# QSD675-Prototype.net
KiCad netlist of a schematic drawn in EAGLE
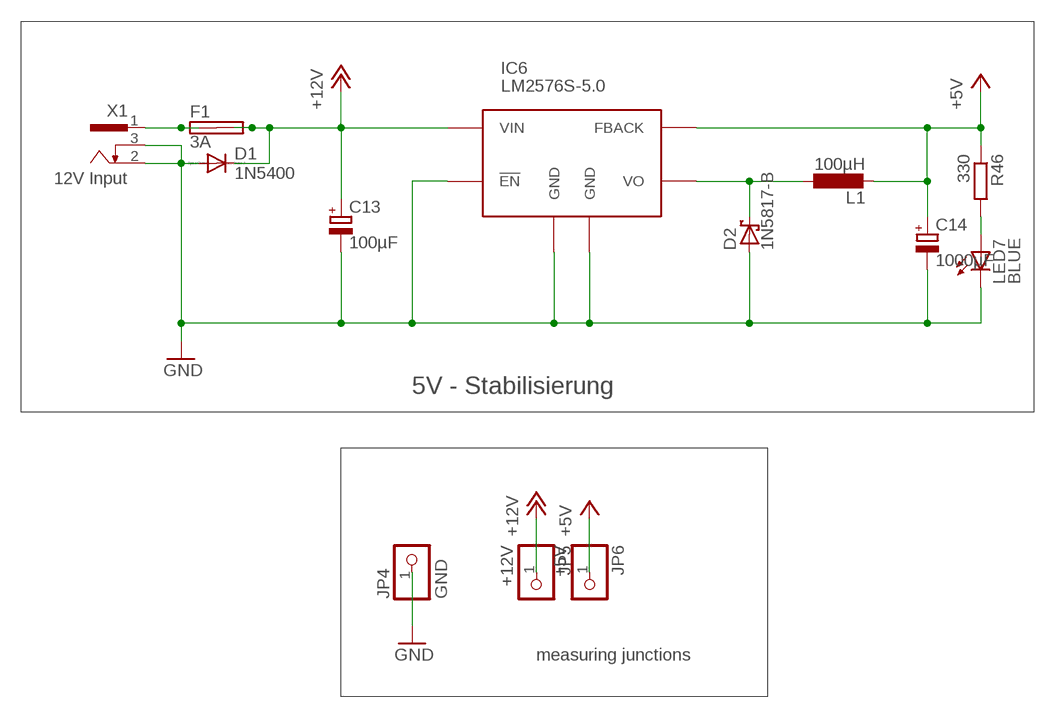
[diagram p0: schematic, sheet 1]
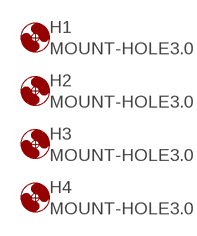
[diagram p1: schematic, sheet 2]
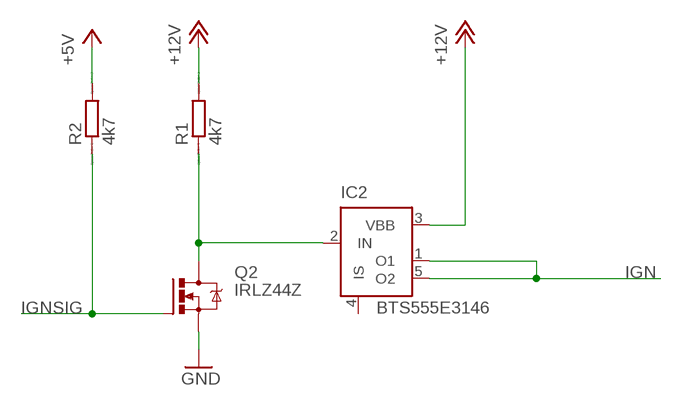
[diagram p2: schematic, sheet 3]
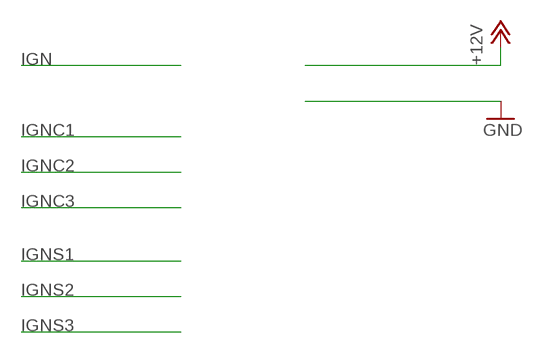
[diagram p3: schematic, sheet 5]
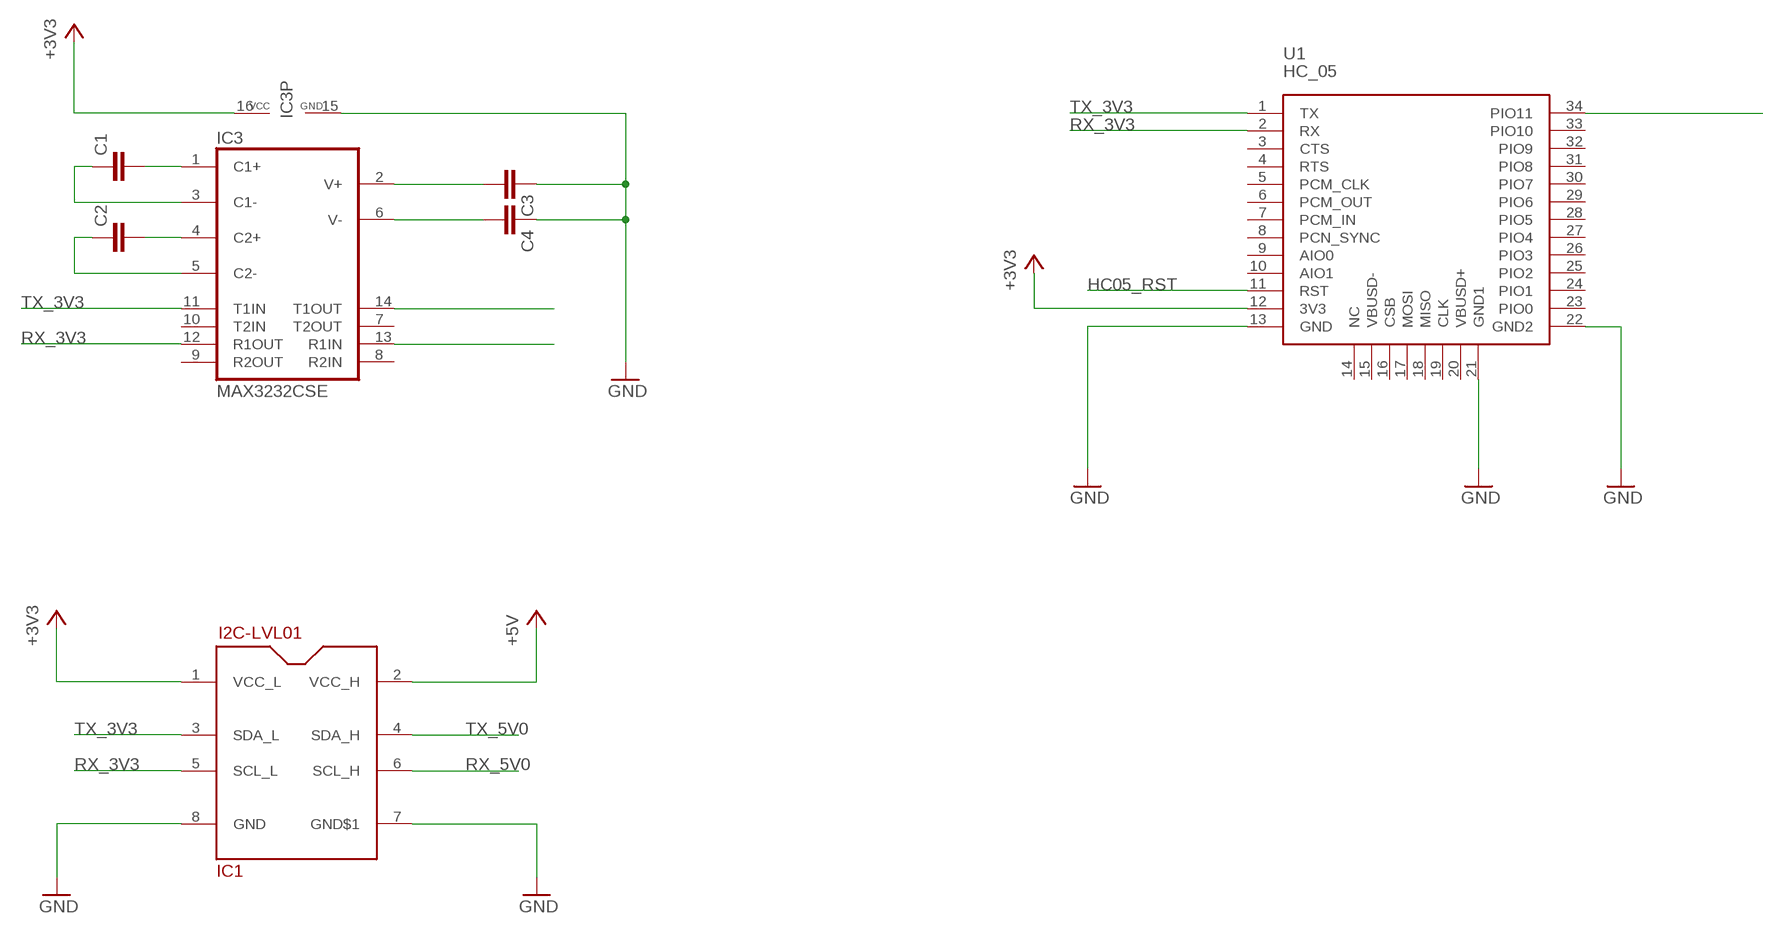
[diagram p4: schematic, sheet 6]

(export (version "E")
  (design (tool "Eeschema 10.0.6"))
  (components
    (comp (ref "C13")
      (value "100µF")
      (footprint "eagle-import:E2,5-7")
      (libsource (lib "eagle-import") (part "CPOL-EUE2.5-7"))
    )
    (comp (ref "C14")
      (value "1000µF")
      (footprint "eagle-import:E5-10,5")
      (libsource (lib "eagle-import") (part "CPOL-EUE5-10.5"))
    )
    (comp (ref "D1")
      (value "1N5400")
      (footprint "eagle-import:DO201-15")
      (libsource (lib "eagle-import") (part "1N5400"))
    )
    (comp (ref "D2")
      (value "1N5817-B")
      (footprint "eagle-import:DO41-7.6")
      (libsource (lib "eagle-import") (part "1N5817-B"))
    )
    (comp (ref "F1")
      (value "3A")
      (footprint "eagle-import:SH32")
      (fields (field (name "MPN") "10207101009"))
      (libsource (lib "eagle-import") (part "SH32"))
    )
    (comp (ref "IC6")
      (value "LM2576S-5.0")
      (footprint "eagle-import:TO263-5")
      (libsource (lib "eagle-import") (part "LM2576S"))
    )
    (comp (ref "JP4")
      (value "GND")
      (footprint "eagle-import:1X01")
      (libsource (lib "eagle-import") (part "PINHD-1X1"))
    )
    (comp (ref "JP5")
      (value "+12V")
      (footprint "eagle-import:1X01")
      (libsource (lib "eagle-import") (part "PINHD-1X1"))
    )
    (comp (ref "JP6")
      (value "+5V")
      (footprint "eagle-import:1X01")
      (libsource (lib "eagle-import") (part "PINHD-1X1"))
    )
    (comp (ref "L1")
      (value "100µH")
      (footprint "eagle-import:0204_5")
      (libsource (lib "eagle-import") (part "L-EU0204/5"))
    )
    (comp (ref "LED7")
      (value "BLUE")
      (footprint "eagle-import:SML0805")
      (libsource (lib "eagle-import") (part "LEDSML0805"))
    )
    (comp (ref "R46")
      (value "330")
      (footprint "eagle-import:M0805")
      (libsource (lib "eagle-import") (part "R-EU_M0805"))
    )
    (comp (ref "X1")
      (value "12V Input")
      (footprint "eagle-import:733980-62")
      (libsource (lib "eagle-import") (part "73398?0-62"))
    )
    (comp (ref "C1")
      (value "C-EUC0805")
      (footprint "eagle-import:C0805")
      (libsource (lib "eagle-import") (part "C-EUC0805"))
    )
    (comp (ref "C2")
      (value "C-EUC0805")
      (footprint "eagle-import:C0805")
      (libsource (lib "eagle-import") (part "C-EUC0805"))
    )
    (comp (ref "C3")
      (value "C-EUC0805")
      (footprint "eagle-import:C0805")
      (libsource (lib "eagle-import") (part "C-EUC0805"))
    )
    (comp (ref "C4")
      (value "C-EUC0805")
      (footprint "eagle-import:C0805")
      (libsource (lib "eagle-import") (part "C-EUC0805"))
    )
    (comp (ref "IC1")
      (value "I2C-LVL01")
      (footprint "eagle-import:I2C-LVL01")
      (libsource (lib "eagle-import") (part "I2C-LVL01"))
    )
    (comp (ref "IC3")
      (value "MAX3232CSE")
      (footprint "eagle-import:SO16")
      (libsource (lib "eagle-import") (part "MAX3232SEC"))
    )
    (comp (ref "U1")
      (value "HC_05")
      (footprint "eagle-import:BLUETOOTH_SMD")
      (libsource (lib "eagle-import") (part "HC_05"))
    )
    (comp (ref "IC2")
      (value "BTS555E3146")
      (footprint "eagle-import:TO220-52")
      (libsource (lib "eagle-import") (part "BTS555E3146"))
    )
    (comp (ref "Q2")
      (value "IRLZ44Z")
      (footprint "eagle-import:TO220BH")
      (libsource (lib "eagle-import") (part "IRLZ44Z"))
    )
    (comp (ref "R1")
      (value "4k7")
      (footprint "eagle-import:R0805")
      (libsource (lib "eagle-import") (part "R"))
    )
    (comp (ref "R2")
      (value "4k7")
      (footprint "eagle-import:R0805")
      (libsource (lib "eagle-import") (part "R"))
    )
    (comp (ref "H1")
      (value "MOUNT-HOLE3.0")
      (footprint "eagle-import:3,0")
      (libsource (lib "eagle-import") (part "MOUNT-HOLE3.0"))
    )
    (comp (ref "H2")
      (value "MOUNT-HOLE3.0")
      (footprint "eagle-import:3,0")
      (libsource (lib "eagle-import") (part "MOUNT-HOLE3.0"))
    )
    (comp (ref "H3")
      (value "MOUNT-HOLE3.0")
      (footprint "eagle-import:3,0")
      (libsource (lib "eagle-import") (part "MOUNT-HOLE3.0"))
    )
    (comp (ref "H4")
      (value "MOUNT-HOLE3.0")
      (footprint "eagle-import:3,0")
      (libsource (lib "eagle-import") (part "MOUNT-HOLE3.0"))
    )
  )
  (nets
    (net (code "1") (name "+3V3") (class "Default")
      (node (ref "IC1") (pin "1") (pinfunction "VCC_L_1") (pintype "power_in"))
      (node (ref "IC3") (pin "16") (pinfunction "VCC_16") (pintype "power_in"))
      (node (ref "U1") (pin "12") (pinfunction "3V3_12") (pintype "bidirectional"))
    )
    (net (code "2") (name "+5V") (class "Default")
      (node (ref "C14") (pin "+") (pinfunction "+_+") (pintype "passive"))
      (node (ref "IC1") (pin "2") (pinfunction "VCC_H_2") (pintype "power_in"))
      (node (ref "IC6") (pin "4") (pinfunction "FBACK_4") (pintype "bidirectional"))
      (node (ref "JP6") (pin "1") (pinfunction "1_1") (pintype "passive"))
      (node (ref "L1") (pin "2") (pinfunction "2_2") (pintype "passive"))
      (node (ref "R2") (pin "2") (pinfunction "2_2") (pintype "passive"))
      (node (ref "R46") (pin "1") (pinfunction "1_1") (pintype "passive"))
    )
    (net (code "3") (name "+12V") (class "Default")
      (node (ref "C13") (pin "+") (pinfunction "+_+") (pintype "passive"))
      (node (ref "D1") (pin "C") (pinfunction "C_C") (pintype "passive"))
      (node (ref "F1") (pin "2A") (pinfunction "2A_2A") (pintype "passive"))
      (node (ref "F1") (pin "2B") (pinfunction "2B_2B") (pintype "passive"))
      (node (ref "IC2") (pin "3") (pinfunction "VBB_3") (pintype "passive"))
      (node (ref "IC6") (pin "1") (pinfunction "VIN_1") (pintype "bidirectional"))
      (node (ref "JP5") (pin "1") (pinfunction "1_1") (pintype "passive"))
      (node (ref "R1") (pin "2") (pinfunction "2_2") (pintype "passive"))
    )
    (net (code "4") (name "GND") (class "Default")
      (node (ref "C13") (pin "-") (pinfunction "-_-") (pintype "passive"))
      (node (ref "C14") (pin "-") (pinfunction "-_-") (pintype "passive"))
      (node (ref "C3") (pin "1") (pinfunction "1_1") (pintype "passive"))
      (node (ref "C4") (pin "1") (pinfunction "1_1") (pintype "passive"))
      (node (ref "D1") (pin "A") (pinfunction "A_A") (pintype "passive"))
      (node (ref "D2") (pin "A") (pinfunction "A_A") (pintype "passive"))
      (node (ref "IC1") (pin "7") (pinfunction "GND$1_7") (pintype "power_in"))
      (node (ref "IC1") (pin "8") (pinfunction "GND_8") (pintype "power_in"))
      (node (ref "IC3") (pin "15") (pinfunction "GND_15") (pintype "power_in"))
      (node (ref "IC6") (pin "3") (pinfunction "GND_3") (pintype "bidirectional"))
      (node (ref "IC6") (pin "5") (pinfunction "~{EN}_5") (pintype "bidirectional"))
      (node (ref "IC6") (pin "TAB") (pinfunction "GND_TAB") (pintype "bidirectional"))
      (node (ref "JP4") (pin "1") (pinfunction "1_1") (pintype "passive"))
      (node (ref "LED7") (pin "C") (pinfunction "C_C") (pintype "passive"))
      (node (ref "Q2") (pin "S") (pinfunction "S_S") (pintype "passive"))
      (node (ref "U1") (pin "13") (pinfunction "GND_13") (pintype "bidirectional"))
      (node (ref "U1") (pin "21") (pinfunction "GND1_21") (pintype "bidirectional"))
      (node (ref "U1") (pin "22") (pinfunction "GND2_22") (pintype "bidirectional"))
      (node (ref "X1") (pin "2") (pinfunction "2_2") (pintype "passive"))
      (node (ref "X1") (pin "3") (pinfunction "3_3") (pintype "passive"))
    )
    (net (code "5") (name "HC05_RST") (class "Default")
      (node (ref "U1") (pin "11") (pinfunction "RST_11") (pintype "bidirectional"))
    )
    (net (code "6") (name "IGN") (class "Default")
      (node (ref "IC2") (pin "1") (pinfunction "O1_1") (pintype "passive"))
      (node (ref "IC2") (pin "5") (pinfunction "O2_5") (pintype "passive"))
    )
    (net (code "13") (name "IGNSIG") (class "Default")
      (node (ref "Q2") (pin "G") (pinfunction "G_G") (pintype "passive"))
      (node (ref "R2") (pin "1") (pinfunction "1_1") (pintype "passive"))
    )
    (net (code "14") (name "Net-(F1-Pad1A)") (class "Default")
      (node (ref "F1") (pin "1A") (pinfunction "1A_1A") (pintype "passive"))
      (node (ref "F1") (pin "1B") (pinfunction "1B_1B") (pintype "passive"))
      (node (ref "X1") (pin "1") (pinfunction "1_1") (pintype "passive"))
    )
    (net (code "15") (name "Net-(IC2-IN)") (class "Default")
      (node (ref "IC2") (pin "2") (pinfunction "IN_2") (pintype "input"))
      (node (ref "Q2") (pin "D") (pinfunction "D_D") (pintype "passive"))
      (node (ref "R1") (pin "1") (pinfunction "1_1") (pintype "passive"))
    )
    (net (code "16") (name "Net-(IC3A-C1+)") (class "Default")
      (node (ref "C1") (pin "2") (pinfunction "2_2") (pintype "passive"))
      (node (ref "IC3") (pin "1") (pinfunction "C1+_1") (pintype "bidirectional"))
    )
    (net (code "17") (name "Net-(IC3A-C1-)") (class "Default")
      (node (ref "C1") (pin "1") (pinfunction "1_1") (pintype "passive"))
      (node (ref "IC3") (pin "3") (pinfunction "C1-_3") (pintype "bidirectional"))
    )
    (net (code "18") (name "Net-(IC3A-C2+)") (class "Default")
      (node (ref "C2") (pin "2") (pinfunction "2_2") (pintype "passive"))
      (node (ref "IC3") (pin "4") (pinfunction "C2+_4") (pintype "bidirectional"))
    )
    (net (code "19") (name "Net-(IC3A-C2-)") (class "Default")
      (node (ref "C2") (pin "1") (pinfunction "1_1") (pintype "passive"))
      (node (ref "IC3") (pin "5") (pinfunction "C2-_5") (pintype "bidirectional"))
    )
    (net (code "20") (name "Net-(IC3A-V+)") (class "Default")
      (node (ref "C3") (pin "2") (pinfunction "2_2") (pintype "passive"))
      (node (ref "IC3") (pin "2") (pinfunction "V+_2") (pintype "bidirectional"))
    )
    (net (code "21") (name "Net-(IC3A-V-)") (class "Default")
      (node (ref "C4") (pin "2") (pinfunction "2_2") (pintype "passive"))
      (node (ref "IC3") (pin "6") (pinfunction "V-_6") (pintype "bidirectional"))
    )
    (net (code "22") (name "Net-(IC6-VO)") (class "Default")
      (node (ref "D2") (pin "C") (pinfunction "C_C") (pintype "passive"))
      (node (ref "IC6") (pin "2") (pinfunction "VO_2") (pintype "bidirectional"))
      (node (ref "L1") (pin "1") (pinfunction "1_1") (pintype "passive"))
    )
    (net (code "23") (name "Net-(LED7-PadA)") (class "Default")
      (node (ref "LED7") (pin "A") (pinfunction "A_A") (pintype "passive"))
      (node (ref "R46") (pin "2") (pinfunction "2_2") (pintype "passive"))
    )
    (net (code "24") (name "RX_3V3") (class "Default")
      (node (ref "IC1") (pin "5") (pinfunction "SCL_L_5") (pintype "bidirectional"))
      (node (ref "IC3") (pin "12") (pinfunction "R1OUT_12") (pintype "output"))
      (node (ref "U1") (pin "2") (pinfunction "RX_2") (pintype "bidirectional"))
    )
    (net (code "25") (name "RX_5V0") (class "Default")
      (node (ref "IC1") (pin "6") (pinfunction "SCL_H_6") (pintype "bidirectional"))
    )
    (net (code "26") (name "TX_3V3") (class "Default")
      (node (ref "IC1") (pin "3") (pinfunction "SDA_L_3") (pintype "bidirectional"))
      (node (ref "IC3") (pin "11") (pinfunction "T1IN_11") (pintype "input"))
      (node (ref "U1") (pin "1") (pinfunction "TX_1") (pintype "bidirectional"))
    )
    (net (code "27") (name "TX_5V0") (class "Default")
      (node (ref "IC1") (pin "4") (pinfunction "SDA_H_4") (pintype "bidirectional"))
    )
    (net (code "28") (name "unconnected-(IC2-IS-Pad4)") (class "Default")
      (node (ref "IC2") (pin "4") (pinfunction "IS_4") (pintype "passive"))
    )
    (net (code "29") (name "unconnected-(IC3A-R1IN-Pad13)") (class "Default")
      (node (ref "IC3") (pin "13") (pinfunction "R1IN_13") (pintype "input"))
    )
    (net (code "30") (name "unconnected-(IC3A-R2IN-Pad8)") (class "Default")
      (node (ref "IC3") (pin "8") (pinfunction "R2IN_8") (pintype "input"))
    )
    (net (code "31") (name "unconnected-(IC3A-R2OUT-Pad9)") (class "Default")
      (node (ref "IC3") (pin "9") (pinfunction "R2OUT_9") (pintype "output"))
    )
    (net (code "32") (name "unconnected-(IC3A-T1OUT-Pad14)") (class "Default")
      (node (ref "IC3") (pin "14") (pinfunction "T1OUT_14") (pintype "output"))
    )
    (net (code "33") (name "unconnected-(IC3A-T2IN-Pad10)") (class "Default")
      (node (ref "IC3") (pin "10") (pinfunction "T2IN_10") (pintype "input"))
    )
    (net (code "34") (name "unconnected-(IC3A-T2OUT-Pad7)") (class "Default")
      (node (ref "IC3") (pin "7") (pinfunction "T2OUT_7") (pintype "output"))
    )
    (net (code "35") (name "unconnected-(U1-AIO0-Pad9)") (class "Default")
      (node (ref "U1") (pin "9") (pinfunction "AIO0_9") (pintype "bidirectional"))
    )
    (net (code "36") (name "unconnected-(U1-AIO1-Pad10)") (class "Default")
      (node (ref "U1") (pin "10") (pinfunction "AIO1_10") (pintype "bidirectional"))
    )
    (net (code "37") (name "unconnected-(U1-CLK-Pad19)") (class "Default")
      (node (ref "U1") (pin "19") (pinfunction "CLK_19") (pintype "bidirectional"))
    )
    (net (code "38") (name "unconnected-(U1-CSB-Pad16)") (class "Default")
      (node (ref "U1") (pin "16") (pinfunction "CSB_16") (pintype "bidirectional"))
    )
    (net (code "39") (name "unconnected-(U1-CTS-Pad3)") (class "Default")
      (node (ref "U1") (pin "3") (pinfunction "CTS_3") (pintype "bidirectional"))
    )
    (net (code "40") (name "unconnected-(U1-MISO-Pad18)") (class "Default")
      (node (ref "U1") (pin "18") (pinfunction "MISO_18") (pintype "bidirectional"))
    )
    (net (code "41") (name "unconnected-(U1-MOSI-Pad17)") (class "Default")
      (node (ref "U1") (pin "17") (pinfunction "MOSI_17") (pintype "bidirectional"))
    )
    (net (code "42") (name "unconnected-(U1-NC-Pad14)") (class "Default")
      (node (ref "U1") (pin "14") (pinfunction "NC_14") (pintype "bidirectional"))
    )
    (net (code "43") (name "unconnected-(U1-PCM_CLK-Pad5)") (class "Default")
      (node (ref "U1") (pin "5") (pinfunction "PCM_CLK_5") (pintype "bidirectional"))
    )
    (net (code "44") (name "unconnected-(U1-PCM_IN-Pad7)") (class "Default")
      (node (ref "U1") (pin "7") (pinfunction "PCM_IN_7") (pintype "bidirectional"))
    )
    (net (code "45") (name "unconnected-(U1-PCM_OUT-Pad6)") (class "Default")
      (node (ref "U1") (pin "6") (pinfunction "PCM_OUT_6") (pintype "bidirectional"))
    )
    (net (code "46") (name "unconnected-(U1-PCN_SYNC-Pad8)") (class "Default")
      (node (ref "U1") (pin "8") (pinfunction "PCN_SYNC_8") (pintype "bidirectional"))
    )
    (net (code "47") (name "unconnected-(U1-PIO0-Pad23)") (class "Default")
      (node (ref "U1") (pin "23") (pinfunction "PIO0_23") (pintype "bidirectional"))
    )
    (net (code "48") (name "unconnected-(U1-PIO1-Pad24)") (class "Default")
      (node (ref "U1") (pin "24") (pinfunction "PIO1_24") (pintype "bidirectional"))
    )
    (net (code "49") (name "unconnected-(U1-PIO2-Pad25)") (class "Default")
      (node (ref "U1") (pin "25") (pinfunction "PIO2_25") (pintype "bidirectional"))
    )
    (net (code "50") (name "unconnected-(U1-PIO3-Pad26)") (class "Default")
      (node (ref "U1") (pin "26") (pinfunction "PIO3_26") (pintype "bidirectional"))
    )
    (net (code "51") (name "unconnected-(U1-PIO4-Pad27)") (class "Default")
      (node (ref "U1") (pin "27") (pinfunction "PIO4_27") (pintype "bidirectional"))
    )
    (net (code "52") (name "unconnected-(U1-PIO5-Pad28)") (class "Default")
      (node (ref "U1") (pin "28") (pinfunction "PIO5_28") (pintype "bidirectional"))
    )
    (net (code "53") (name "unconnected-(U1-PIO6-Pad29)") (class "Default")
      (node (ref "U1") (pin "29") (pinfunction "PIO6_29") (pintype "bidirectional"))
    )
    (net (code "54") (name "unconnected-(U1-PIO7-Pad30)") (class "Default")
      (node (ref "U1") (pin "30") (pinfunction "PIO7_30") (pintype "bidirectional"))
    )
    (net (code "55") (name "unconnected-(U1-PIO8-Pad31)") (class "Default")
      (node (ref "U1") (pin "31") (pinfunction "PIO8_31") (pintype "bidirectional"))
    )
    (net (code "56") (name "unconnected-(U1-PIO9-Pad32)") (class "Default")
      (node (ref "U1") (pin "32") (pinfunction "PIO9_32") (pintype "bidirectional"))
    )
    (net (code "57") (name "unconnected-(U1-PIO10-Pad33)") (class "Default")
      (node (ref "U1") (pin "33") (pinfunction "PIO10_33") (pintype "bidirectional"))
    )
    (net (code "58") (name "unconnected-(U1-PIO11-Pad34)") (class "Default")
      (node (ref "U1") (pin "34") (pinfunction "PIO11_34") (pintype "bidirectional"))
    )
    (net (code "59") (name "unconnected-(U1-RTS-Pad4)") (class "Default")
      (node (ref "U1") (pin "4") (pinfunction "RTS_4") (pintype "bidirectional"))
    )
    (net (code "60") (name "unconnected-(U1-VBUSD+-Pad20)") (class "Default")
      (node (ref "U1") (pin "20") (pinfunction "VBUSD+_20") (pintype "bidirectional"))
    )
    (net (code "61") (name "unconnected-(U1-VBUSD--Pad15)") (class "Default")
      (node (ref "U1") (pin "15") (pinfunction "VBUSD-_15") (pintype "bidirectional"))
    )
  )
)
